# 2_SurvBot_RCU_MCU.net
KiCad netlist of a schematic drawn in Altium Designer
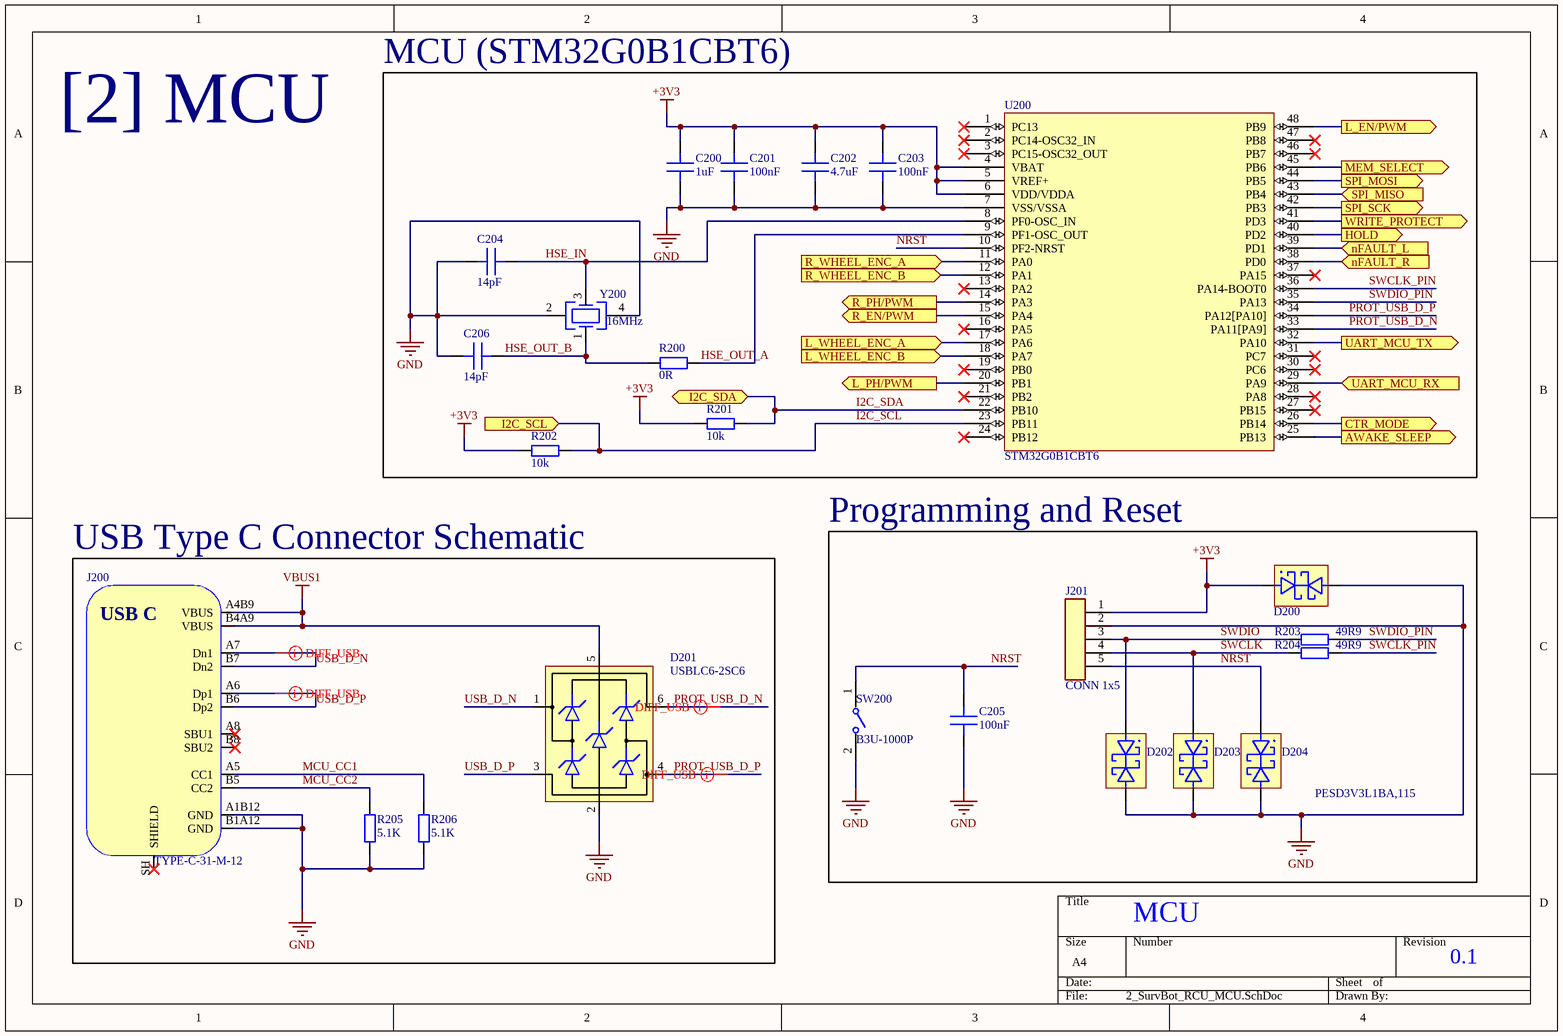
[diagram p0: 2_SurvBot_RCU_MCU.SchDoc]

(export (version "E")
  (design (tool "Eeschema 10.0.6"))
  (components
    (comp (ref "C200")
      (value "1uF")
      (footprint "CAP_0402")
      (description "1 µF ±10% 16V Ceramic Capacitor X5R 0402 (1005 Metric)")
      (fields
        (field (name "MANUFACTURER") "Samsung Electro-Mechanics")
        (field (name "MANUFACTURER PART #") "CL05A105KO5NNNC")
      )
      (libsource (lib "GhaniLibrary") (part "CAP_1uF-16V-10%-0402"))
    )
    (comp (ref "C201")
      (value "100nF")
      (footprint "CAP_0402")
      (description "0.1 µF ±10% 10V Ceramic Capacitor X7R 0402 (1005 Metric)")
      (fields
        (field (name "MANUFACTURER") "Samsung Electro-Mechanics")
        (field (name "MANUFACTURER PART #") "CL05B104KP5NNNC")
      )
      (libsource (lib "GhaniLibrary") (part "CAP_100nF-10V-10%-0402"))
    )
    (comp (ref "C202")
      (value "4.7uF")
      (footprint "CAP_0402")
      (description "4.7 µF ±20% 10V Ceramic Capacitor X5R 0402 (1005 Metric)")
      (fields
        (field (name "MANUFACTURER") "Samsung Electro-Mechanics")
        (field (name "MANUFACTURER PART #") "CL05A475MP5NRNC")
      )
      (libsource (lib "GhaniLibrary") (part "CAP_4.7uF-10V-20%-0402"))
    )
    (comp (ref "C203")
      (value "100nF")
      (footprint "CAP_0402")
      (description "0.1 µF ±10% 10V Ceramic Capacitor X7R 0402 (1005 Metric)")
      (fields
        (field (name "MANUFACTURER") "Samsung Electro-Mechanics")
        (field (name "MANUFACTURER PART #") "CL05B104KP5NNNC")
      )
      (libsource (lib "GhaniLibrary") (part "CAP_100nF-10V-10%-0402"))
    )
    (comp (ref "C204")
      (value "14pF")
      (footprint "CAP_0402")
      (description "50V 14pF NP0 ±5% 0402 Multilayer Ceramic Capacitors MLCC - SMD/SMT ROHS")
      (fields
        (field (name "MANUFACTURER") "Walsin Tech Corp")
        (field (name "MANUFACTURER PART #") "0402N140J500CT")
      )
      (libsource (lib "GhaniLibrary") (part "CAP_14pF-50V-5%-0402"))
    )
    (comp (ref "C205")
      (value "100nF")
      (footprint "CAP_0402")
      (description "0.1 µF ±10% 10V Ceramic Capacitor X7R 0402 (1005 Metric)")
      (fields
        (field (name "MANUFACTURER") "Samsung Electro-Mechanics")
        (field (name "MANUFACTURER PART #") "CL05B104KP5NNNC")
      )
      (libsource (lib "GhaniLibrary") (part "CAP_100nF-10V-10%-0402"))
    )
    (comp (ref "C206")
      (value "14pF")
      (footprint "CAP_0402")
      (description "50V 14pF NP0 ±5% 0402 Multilayer Ceramic Capacitors MLCC - SMD/SMT ROHS")
      (fields
        (field (name "MANUFACTURER") "Walsin Tech Corp")
        (field (name "MANUFACTURER PART #") "0402N140J500CT")
      )
      (libsource (lib "GhaniLibrary") (part "CAP_14pF-50V-5%-0402"))
    )
    (comp (ref "D200")
      (value "PESD3V3L1BA,115")
      (footprint "SC-76, SOD-323")
      (description "26V Clamp 18A (8/20µs) Ipp Tvs Diode Surface Mount SOD-323")
      (fields (field (name "MANUFACTURER") "Nexperia"))
      (libsource (lib "") (part "DIO-TVS_3.3V-26V-18A-SOD-323_1"))
    )
    (comp (ref "D201")
      (value "USBLC6-2SC6")
      (footprint "SOT-23-6")
      (description "Low-Capacitance ESD Protection USB")
      (fields (field (name "MANUFACTURER") "STMicroelectronics"))
      (libsource (lib "Schematic-Lib-PhilsLab") (part "USBLC6-2SC6"))
    )
    (comp (ref "D202")
      (value "PESD3V3L1BA,115")
      (footprint "SC-76, SOD-323")
      (description "26V Clamp 18A (8/20µs) Ipp Tvs Diode Surface Mount SOD-323")
      (fields (field (name "MANUFACTURER") "Nexperia"))
      (libsource (lib "GhaniLibrary") (part "DIO-TVS_3.3V-26V-18A-SOD-323"))
    )
    (comp (ref "D203")
      (value "PESD3V3L1BA,115")
      (footprint "SC-76, SOD-323")
      (description "26V Clamp 18A (8/20µs) Ipp Tvs Diode Surface Mount SOD-323")
      (fields (field (name "MANUFACTURER") "Nexperia"))
      (libsource (lib "GhaniLibrary") (part "DIO-TVS_3.3V-26V-18A-SOD-323"))
    )
    (comp (ref "D204")
      (value "PESD3V3L1BA,115")
      (footprint "SC-76, SOD-323")
      (description "26V Clamp 18A (8/20µs) Ipp Tvs Diode Surface Mount SOD-323")
      (fields (field (name "MANUFACTURER") "Nexperia"))
      (libsource (lib "GhaniLibrary") (part "DIO-TVS_3.3V-26V-18A-SOD-323"))
    )
    (comp (ref "J200")
      (value "TYPE-C-31-M-12")
      (footprint "USB4105-GF-A-060")
      (description "5A 1 16P Female Type-C SMD USB Connectors ROHS")
      (fields (field (name "MANUFACTURER") "Korean Hroparts Elec"))
      (libsource (lib "Schematic-Lib-PhilsLab") (part "USB4105-GF-A-060_1"))
    )
    (comp (ref "J201")
      (value "CONN 1x5")
      (footprint "2541FV-5P")
      (fields (field (name "MANUFACTURER") "HanElectricity") (field (name "MANUFACTURER PART #") "2541FV-5P"))
      (libsource (lib "GhaniLibrary") (part "CONN_5_HDR_0.1-2541FV-5P"))
    )
    (comp (ref "R200")
      (value "0R")
      (footprint "RES_0402")
      (description "0 Ohms Jumper Chip Resistor 0402 (1005 Metric) Moisture Resistant Thick Film")
      (fields (field (name "MANUFACTURER") "YAGEO") (field (name "MANUFACTURER PART #") "RC0402JR-070RL"))
      (libsource (lib "GhaniLibrary") (part "RES_0R-62.5mW-5%-0402"))
    )
    (comp (ref "R201")
      (value "10k")
      (footprint "RES_0402")
      (description "10 kOhms ±1% 0.063W, 1/16W Chip Resistor 0402 (1005 Metric) Moisture Resistant Thick Film")
      (fields (field (name "MANUFACTURER") "YAGEO") (field (name "MANUFACTURER PART #") "RC0402FR-0710KL"))
      (libsource (lib "GhaniLibrary") (part "RES_10K-62.5mW-1%-0402"))
    )
    (comp (ref "R202")
      (value "10k")
      (footprint "RES_0402")
      (description "10 kOhms ±1% 0.063W, 1/16W Chip Resistor 0402 (1005 Metric) Moisture Resistant Thick Film")
      (fields (field (name "MANUFACTURER") "YAGEO") (field (name "MANUFACTURER PART #") "RC0402FR-0710KL"))
      (libsource (lib "GhaniLibrary") (part "RES_10K-62.5mW-1%-0402"))
    )
    (comp (ref "R203")
      (value "49R9")
      (footprint "RES_0603")
      (description "49.9 Ohms ±1% 0.1W, 1/10W Chip Resistor 0603 (1608 Metric) Automotive AEC-Q200 Thick Film")
      (fields (field (name "MANUFACTURER") "PANASONIC") (field (name "MANUFACTURER PART #") "ERJ3EKF49R9V"))
      (libsource (lib "GhaniLibrary") (part "RES_49.R9-100mW-1%-0603"))
    )
    (comp (ref "R204")
      (value "49R9")
      (footprint "RES_0603")
      (description "49.9 Ohms ±1% 0.1W, 1/10W Chip Resistor 0603 (1608 Metric) Automotive AEC-Q200 Thick Film")
      (fields (field (name "MANUFACTURER") "PANASONIC") (field (name "MANUFACTURER PART #") "ERJ3EKF49R9V"))
      (libsource (lib "GhaniLibrary") (part "RES_49.R9-100mW-1%-0603"))
    )
    (comp (ref "R205")
      (value "5.1K")
      (footprint "RES_0603")
      (description "5.1 kOhms ±1% 0.1W, 1/10W Chip Resistor 0603 (1608 Metric) Moisture Resistant Thick Film")
      (fields (field (name "MANUFACTURER") "YAGEO") (field (name "MANUFACTURER PART #") "RC0603FR-075K1L"))
      (libsource (lib "GhaniLibrary") (part "RES_5.1K-100mW-1%-0603"))
    )
    (comp (ref "R206")
      (value "5.1K")
      (footprint "RES_0603")
      (description "5.1 kOhms ±1% 0.1W, 1/10W Chip Resistor 0603 (1608 Metric) Moisture Resistant Thick Film")
      (fields (field (name "MANUFACTURER") "YAGEO") (field (name "MANUFACTURER PART #") "RC0603FR-075K1L"))
      (libsource (lib "GhaniLibrary") (part "RES_5.1K-100mW-1%-0603"))
    )
    (comp (ref "SW200")
      (value "B3U-1000P")
      (footprint "FP-B3U-1000P-MFG")
      (description "SWITCH TACTILE SPST-NO 0.05A 12V")
      (fields (field (name "MANUFACTURER") "Omron Electronics"))
      (libsource (lib "Altium Content Vault") (part "ae622034201233ca1abcedc05908f33"))
    )
    (comp (ref "U200")
      (value "STM32G0B1CBT6")
      (footprint "48-LQFP (7x7mm)")
      (fields (field (name "MANUFACTURER") "STMicroelectronics"))
      (libsource (lib "GhaniLibrary") (part "STM32G0B1CBT6"))
    )
    (comp (ref "Y200")
      (value "16MHz")
      (footprint "SMD3225-4P")
      (description "16MHz SMD crystal oscillator 12pF ±10ppm ±30ppm SMD3225-4P Crystals ROHS")
      (fields
        (field (name "MANUFACTURER") "SJK(SHENZHEN CRYSTAL TECH)")
        (field (name "MANUFACTURER PART #") "7U16000E12UCG")
      )
      (libsource (lib "GhaniLibrary") (part "XTAL_16MHz_SMD3225-4P"))
    )
  )
  (nets
    (net (code "1") (name "+3V3") (class "Default")
      (node (ref "C200") (pin "2") (pinfunction "0_2") (pintype "passive"))
      (node (ref "C201") (pin "2") (pinfunction "0_2") (pintype "passive"))
      (node (ref "C202") (pin "2") (pinfunction "0_2") (pintype "passive"))
      (node (ref "C203") (pin "2") (pinfunction "0_2") (pintype "passive"))
      (node (ref "D200") (pin "K1") (pinfunction "1_K1") (pintype "passive"))
      (node (ref "J201") (pin "1") (pintype "passive"))
      (node (ref "R201") (pin "1") (pinfunction "1_1") (pintype "passive"))
      (node (ref "R202") (pin "2") (pinfunction "2_2") (pintype "passive"))
      (node (ref "U200") (pin "4") (pinfunction "VBAT_4") (pintype "power_in"))
      (node (ref "U200") (pin "5") (pinfunction "VREF+_5") (pintype "power_in"))
      (node (ref "U200") (pin "6") (pinfunction "VDD/VDDA_6") (pintype "power_in"))
    )
    (net (code "2") (name "/AWAKE_SLEEP") (class "Default")
      (node (ref "U200") (pin "25") (pinfunction "PB13_25") (pintype "bidirectional"))
    )
    (net (code "3") (name "/CTR_MODE") (class "Default")
      (node (ref "U200") (pin "26") (pinfunction "PB14_26") (pintype "bidirectional"))
    )
    (net (code "4") (name "/HOLD") (class "Default")
      (node (ref "U200") (pin "40") (pinfunction "PD2_40") (pintype "bidirectional"))
    )
    (net (code "5") (name "/HSE_IN") (class "Default")
      (node (ref "C204") (pin "2") (pinfunction "0_2") (pintype "passive"))
      (node (ref "U200") (pin "8") (pinfunction "PF0-OSC_IN_8") (pintype "bidirectional"))
      (node (ref "Y200") (pin "3") (pinfunction "OSC_3") (pintype "passive"))
    )
    (net (code "6") (name "/HSE_OUT_A") (class "Default")
      (node (ref "R200") (pin "2") (pinfunction "2_2") (pintype "passive"))
      (node (ref "U200") (pin "9") (pinfunction "PF1-OSC_OUT_9") (pintype "bidirectional"))
    )
    (net (code "7") (name "/HSE_OUT_B") (class "Default")
      (node (ref "C206") (pin "2") (pinfunction "0_2") (pintype "passive"))
      (node (ref "R200") (pin "1") (pinfunction "1_1") (pintype "passive"))
      (node (ref "Y200") (pin "1") (pinfunction "OSC_1") (pintype "passive"))
    )
    (net (code "8") (name "/I2C_SCL") (class "Default")
      (node (ref "R202") (pin "1") (pinfunction "1_1") (pintype "passive"))
      (node (ref "U200") (pin "23") (pinfunction "PB11_23") (pintype "bidirectional"))
    )
    (net (code "9") (name "/I2C_SDA") (class "Default")
      (node (ref "R201") (pin "2") (pinfunction "2_2") (pintype "passive"))
      (node (ref "U200") (pin "22") (pinfunction "PB10_22") (pintype "bidirectional"))
    )
    (net (code "10") (name "/L_EN{slash}PWM") (class "Default")
      (node (ref "U200") (pin "48") (pinfunction "PB9_48") (pintype "bidirectional"))
    )
    (net (code "11") (name "/L_PH{slash}PWM") (class "Default")
      (node (ref "U200") (pin "20") (pinfunction "PB1_20") (pintype "bidirectional"))
    )
    (net (code "12") (name "/L_WHEEL_ENC_A") (class "Default")
      (node (ref "U200") (pin "17") (pinfunction "PA6_17") (pintype "bidirectional"))
    )
    (net (code "13") (name "/L_WHEEL_ENC_B") (class "Default")
      (node (ref "U200") (pin "18") (pinfunction "PA7_18") (pintype "bidirectional"))
    )
    (net (code "14") (name "/MCU_CC1") (class "Default")
      (node (ref "J200") (pin "A5") (pinfunction "CC1_A5") (pintype "passive"))
      (node (ref "R206") (pin "2") (pinfunction "2_2") (pintype "passive"))
    )
    (net (code "15") (name "/MCU_CC2") (class "Default")
      (node (ref "J200") (pin "B5") (pinfunction "CC2_B5") (pintype "passive"))
      (node (ref "R205") (pin "2") (pinfunction "2_2") (pintype "passive"))
    )
    (net (code "16") (name "/MEM_SELECT") (class "Default")
      (node (ref "U200") (pin "45") (pinfunction "PB6_45") (pintype "bidirectional"))
    )
    (net (code "17") (name "/NRST") (class "Default")
      (node (ref "C205") (pin "2") (pinfunction "0_2") (pintype "passive"))
      (node (ref "D204") (pin "K1") (pinfunction "1_K1") (pintype "passive"))
      (node (ref "J201") (pin "5") (pinfunction "5_5") (pintype "passive"))
      (node (ref "SW200") (pin "1") (pinfunction "1_1") (pintype "passive"))
      (node (ref "U200") (pin "10") (pinfunction "PF2-NRST_10") (pintype "bidirectional"))
    )
    (net (code "18") (name "/PROT_USB_D_N") (class "Default")
      (node (ref "D201") (pin "6") (pinfunction "IO1_6") (pintype "bidirectional"))
      (node (ref "U200") (pin "33") (pinfunction "PA11[PA9]_33") (pintype "bidirectional"))
    )
    (net (code "19") (name "/PROT_USB_D_P") (class "Default")
      (node (ref "D201") (pin "4") (pinfunction "IO2_4") (pintype "bidirectional"))
      (node (ref "U200") (pin "34") (pinfunction "PA12[PA10]_34") (pintype "bidirectional"))
    )
    (net (code "20") (name "/R_EN{slash}PWM") (class "Default")
      (node (ref "U200") (pin "15") (pinfunction "PA4_15") (pintype "bidirectional"))
    )
    (net (code "21") (name "/R_PH{slash}PWM") (class "Default")
      (node (ref "U200") (pin "14") (pinfunction "PA3_14") (pintype "bidirectional"))
    )
    (net (code "22") (name "/R_WHEEL_ENC_A") (class "Default")
      (node (ref "U200") (pin "11") (pinfunction "PA0_11") (pintype "bidirectional"))
    )
    (net (code "23") (name "/R_WHEEL_ENC_B") (class "Default")
      (node (ref "U200") (pin "12") (pinfunction "PA1_12") (pintype "bidirectional"))
    )
    (net (code "24") (name "/SPI_MISO") (class "Default")
      (node (ref "U200") (pin "43") (pinfunction "PB4_43") (pintype "bidirectional"))
    )
    (net (code "25") (name "/SPI_MOSI") (class "Default")
      (node (ref "U200") (pin "44") (pinfunction "PB5_44") (pintype "bidirectional"))
    )
    (net (code "26") (name "/SPI_SCK") (class "Default")
      (node (ref "U200") (pin "42") (pinfunction "PB3_42") (pintype "bidirectional"))
    )
    (net (code "27") (name "/SWCLK") (class "Default")
      (node (ref "D203") (pin "K1") (pinfunction "1_K1") (pintype "passive"))
      (node (ref "J201") (pin "4") (pinfunction "4_4") (pintype "passive"))
      (node (ref "R204") (pin "1") (pinfunction "1_1") (pintype "passive"))
    )
    (net (code "28") (name "/SWCLK_PIN") (class "Default")
      (node (ref "R204") (pin "2") (pinfunction "2_2") (pintype "passive"))
      (node (ref "U200") (pin "36") (pinfunction "PA14-BOOT0_36") (pintype "bidirectional"))
    )
    (net (code "29") (name "/SWDIO") (class "Default")
      (node (ref "D202") (pin "K1") (pinfunction "1_K1") (pintype "passive"))
      (node (ref "J201") (pin "3") (pinfunction "3_3") (pintype "passive"))
      (node (ref "R203") (pin "1") (pinfunction "1_1") (pintype "passive"))
    )
    (net (code "30") (name "/SWDIO_PIN") (class "Default")
      (node (ref "R203") (pin "2") (pinfunction "2_2") (pintype "passive"))
      (node (ref "U200") (pin "35") (pinfunction "PA13_35") (pintype "bidirectional"))
    )
    (net (code "31") (name "/UART_MCU_RX") (class "Default")
      (node (ref "U200") (pin "29") (pinfunction "PA9_29") (pintype "bidirectional"))
    )
    (net (code "32") (name "/UART_MCU_TX") (class "Default")
      (node (ref "U200") (pin "32") (pinfunction "PA10_32") (pintype "bidirectional"))
    )
    (net (code "33") (name "/USB_D_N") (class "Default")
      (node (ref "D201") (pin "1") (pinfunction "IO1_1") (pintype "bidirectional"))
      (node (ref "J200") (pin "A7") (pinfunction "Dn1_A7") (pintype "passive"))
      (node (ref "J200") (pin "B7") (pinfunction "Dn2_B7") (pintype "passive"))
    )
    (net (code "34") (name "/USB_D_P") (class "Default")
      (node (ref "D201") (pin "3") (pinfunction "IO2_3") (pintype "bidirectional"))
      (node (ref "J200") (pin "A6") (pinfunction "Dp1_A6") (pintype "passive"))
      (node (ref "J200") (pin "B6") (pinfunction "Dp2_B6") (pintype "passive"))
    )
    (net (code "35") (name "/WRITE_PROTECT") (class "Default")
      (node (ref "U200") (pin "41") (pinfunction "PD3_41") (pintype "bidirectional"))
    )
    (net (code "36") (name "/nFAULT_L") (class "Default")
      (node (ref "U200") (pin "39") (pinfunction "PD1_39") (pintype "bidirectional"))
    )
    (net (code "37") (name "/nFAULT_R") (class "Default")
      (node (ref "U200") (pin "38") (pinfunction "PD0_38") (pintype "bidirectional"))
    )
    (net (code "38") (name "GND") (class "Default")
      (node (ref "C200") (pin "1") (pinfunction "0_1") (pintype "passive"))
      (node (ref "C201") (pin "1") (pinfunction "0_1") (pintype "passive"))
      (node (ref "C202") (pin "1") (pinfunction "0_1") (pintype "passive"))
      (node (ref "C203") (pin "1") (pinfunction "0_1") (pintype "passive"))
      (node (ref "C204") (pin "1") (pinfunction "0_1") (pintype "passive"))
      (node (ref "C205") (pin "1") (pinfunction "0_1") (pintype "passive"))
      (node (ref "C206") (pin "1") (pinfunction "0_1") (pintype "passive"))
      (node (ref "D200") (pin "K2") (pinfunction "2_K2") (pintype "passive"))
      (node (ref "D201") (pin "2") (pinfunction "GND_2") (pintype "power_in"))
      (node (ref "D202") (pin "K2") (pinfunction "2_K2") (pintype "passive"))
      (node (ref "D203") (pin "K2") (pinfunction "2_K2") (pintype "passive"))
      (node (ref "D204") (pin "K2") (pinfunction "2_K2") (pintype "passive"))
      (node (ref "J200") (pin "A1B12") (pinfunction "GND_A1B12") (pintype "passive"))
      (node (ref "J200") (pin "B1A12") (pinfunction "GND_B1A12") (pintype "passive"))
      (node (ref "J201") (pin "2") (pinfunction "2_2") (pintype "passive"))
      (node (ref "R205") (pin "1") (pinfunction "1_1") (pintype "passive"))
      (node (ref "R206") (pin "1") (pinfunction "1_1") (pintype "passive"))
      (node (ref "SW200") (pin "2") (pinfunction "2_2") (pintype "passive"))
      (node (ref "U200") (pin "7") (pinfunction "VSS/VSSA_7") (pintype "power_in"))
      (node (ref "Y200") (pin "2") (pinfunction "GND_2") (pintype "power_in"))
      (node (ref "Y200") (pin "4") (pinfunction "GND_4") (pintype "power_in"))
    )
    (net (code "39") (name "VBUS1") (class "Default")
      (node (ref "D201") (pin "5") (pinfunction "VBUS_5") (pintype "power_in"))
      (node (ref "J200") (pin "A4B9") (pinfunction "VBUS_A4B9") (pintype "passive"))
      (node (ref "J200") (pin "B4A9") (pinfunction "VBUS_B4A9") (pintype "passive"))
    )
    (net (code "40") (name "unconnected-(J200-SBU1-PadA8)") (class "Default")
      (node (ref "J200") (pin "A8") (pinfunction "SBU1_A8") (pintype "passive+no_connect"))
    )
    (net (code "41") (name "unconnected-(J200-SBU2-PadB8)") (class "Default")
      (node (ref "J200") (pin "B8") (pinfunction "SBU2_B8") (pintype "passive+no_connect"))
    )
    (net (code "42") (name "unconnected-(J200-SHIELD-PadSH)") (class "Default")
      (node (ref "J200") (pin "SH") (pinfunction "SHIELD_SH") (pintype "passive+no_connect"))
    )
    (net (code "43") (name "unconnected-(U200-PA2-Pad13)") (class "Default")
      (node (ref "U200") (pin "13") (pinfunction "PA2_13") (pintype "bidirectional+no_connect"))
    )
    (net (code "44") (name "unconnected-(U200-PA5-Pad16)") (class "Default")
      (node (ref "U200") (pin "16") (pinfunction "PA5_16") (pintype "bidirectional+no_connect"))
    )
    (net (code "45") (name "unconnected-(U200-PA8-Pad28)") (class "Default")
      (node (ref "U200") (pin "28") (pinfunction "PA8_28") (pintype "bidirectional+no_connect"))
    )
    (net (code "46") (name "unconnected-(U200-PA15-Pad37)") (class "Default")
      (node (ref "U200") (pin "37") (pinfunction "PA15_37") (pintype "bidirectional+no_connect"))
    )
    (net (code "47") (name "unconnected-(U200-PB0-Pad19)") (class "Default")
      (node (ref "U200") (pin "19") (pinfunction "PB0_19") (pintype "bidirectional+no_connect"))
    )
    (net (code "48") (name "unconnected-(U200-PB2-Pad21)") (class "Default")
      (node (ref "U200") (pin "21") (pinfunction "PB2_21") (pintype "bidirectional+no_connect"))
    )
    (net (code "49") (name "unconnected-(U200-PB7-Pad46)") (class "Default")
      (node (ref "U200") (pin "46") (pinfunction "PB7_46") (pintype "bidirectional+no_connect"))
    )
    (net (code "50") (name "unconnected-(U200-PB8-Pad47)") (class "Default")
      (node (ref "U200") (pin "47") (pinfunction "PB8_47") (pintype "bidirectional+no_connect"))
    )
    (net (code "51") (name "unconnected-(U200-PB12-Pad24)") (class "Default")
      (node (ref "U200") (pin "24") (pinfunction "PB12_24") (pintype "bidirectional+no_connect"))
    )
    (net (code "52") (name "unconnected-(U200-PB15-Pad27)") (class "Default")
      (node (ref "U200") (pin "27") (pinfunction "PB15_27") (pintype "bidirectional+no_connect"))
    )
    (net (code "53") (name "unconnected-(U200-PC6-Pad30)") (class "Default")
      (node (ref "U200") (pin "30") (pinfunction "PC6_30") (pintype "bidirectional+no_connect"))
    )
    (net (code "54") (name "unconnected-(U200-PC7-Pad31)") (class "Default")
      (node (ref "U200") (pin "31") (pinfunction "PC7_31") (pintype "bidirectional+no_connect"))
    )
    (net (code "55") (name "unconnected-(U200-PC13-Pad1)") (class "Default")
      (node (ref "U200") (pin "1") (pinfunction "PC13_1") (pintype "bidirectional+no_connect"))
    )
    (net (code "56") (name "unconnected-(U200-PC14-OSC32_IN-Pad2)") (class "Default")
      (node (ref "U200") (pin "2") (pinfunction "PC14-OSC32_IN_2") (pintype "bidirectional+no_connect"))
    )
    (net (code "57") (name "unconnected-(U200-PC15-OSC32_OUT-Pad3)") (class "Default")
      (node (ref "U200") (pin "3") (pinfunction "PC15-OSC32_OUT_3") (pintype "bidirectional+no_connect"))
    )
  )
)
